# ATM90E2x-DB.net
KiCad netlist of a schematic drawn in Altium Designer
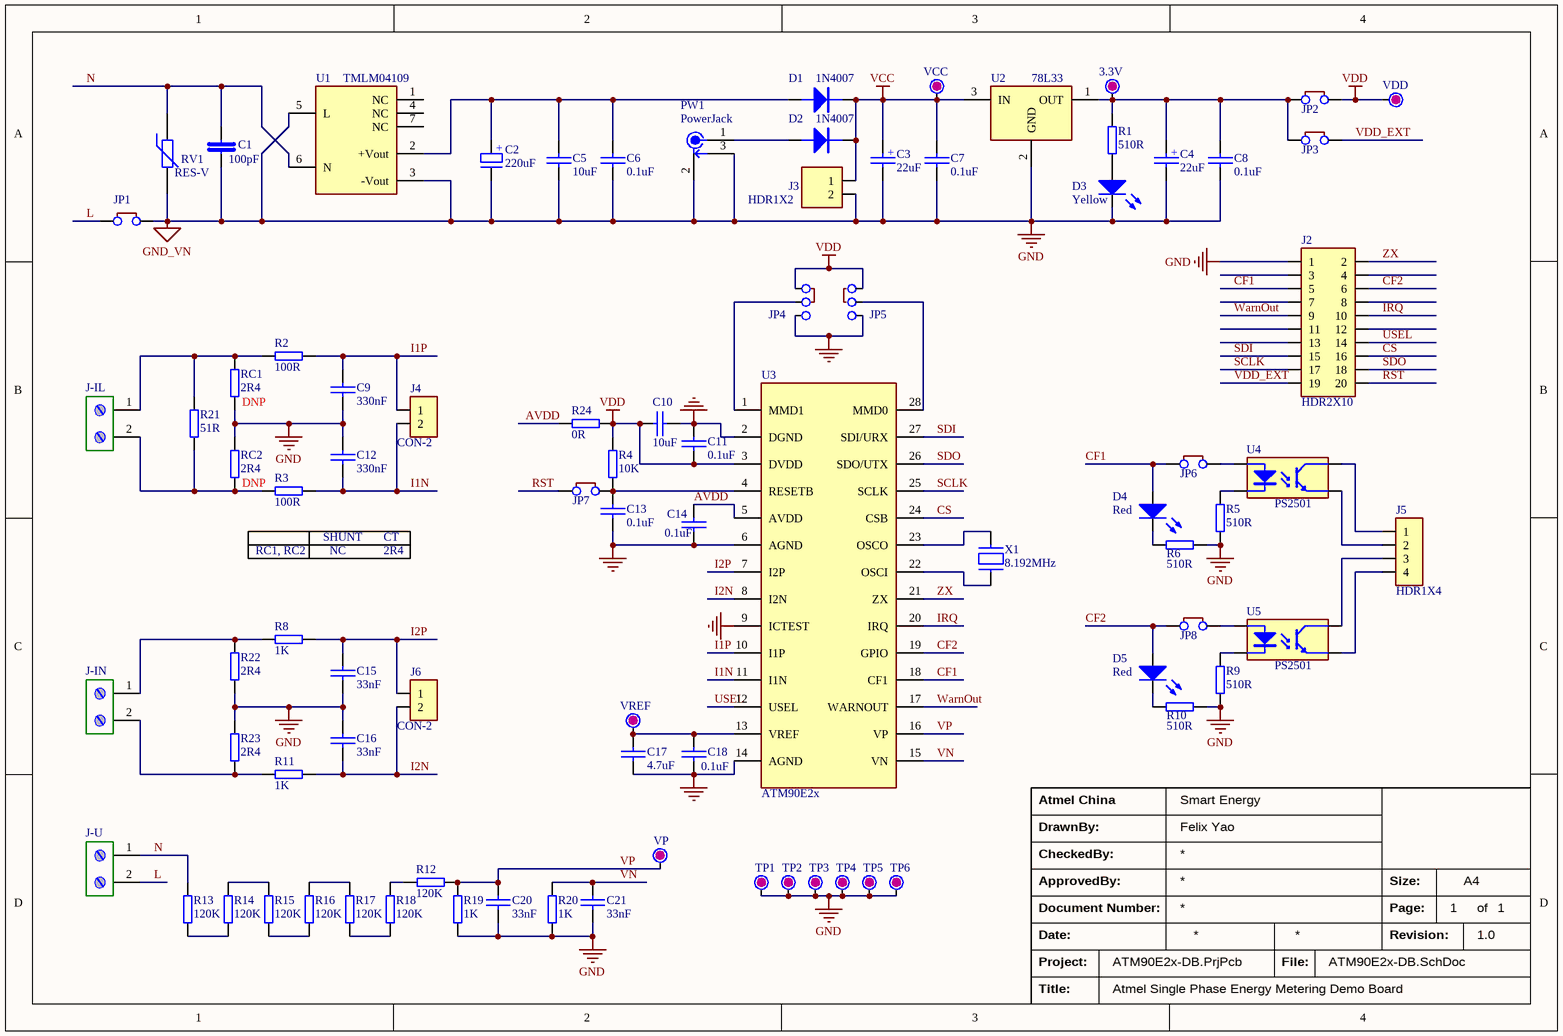
[diagram p0: ATM90E2x-DB.SchDoc]

(export (version "E")
  (design (tool "Eeschema 10.0.6"))
  (components
    (comp (ref "3.3V")
      (value "TEST-POINT")
      (footprint "TP")
      (libsource (lib "SchLib(AD10)") (part "TEST-POINT"))
    )
    (comp (ref "C1")
      (value "100pF")
      (footprint "C_FILM_600")
      (libsource (lib "SchLib(AD10)") (part "CAP-FILM"))
    )
    (comp (ref "C2")
      (value "220uF")
      (footprint "C_ALUM_MIX_10x10")
      (libsource (lib "SchLib(AD10)") (part "CAP-ALUM"))
    )
    (comp (ref "C3")
      (value "22uF")
      (footprint "C_TANT_B3528")
      (libsource (lib "SchLib(AD10)") (part "CAP-TANT"))
    )
    (comp (ref "C4")
      (value "22uF")
      (footprint "C_TANT_B3528")
      (libsource (lib "SchLib(AD10)") (part "CAP-TANT"))
    )
    (comp (ref "C5") (value "10uF") (footprint "C0805") (libsource (lib "SchLib(AD10)") (part "CAP")))
    (comp (ref "C6") (value "0.1uF") (footprint "C0805") (libsource (lib "SchLib(AD10)") (part "CAP")))
    (comp (ref "C7") (value "0.1uF") (footprint "C0805") (libsource (lib "SchLib(AD10)") (part "CAP")))
    (comp (ref "C8") (value "0.1uF") (footprint "C0805") (libsource (lib "SchLib(AD10)") (part "CAP")))
    (comp (ref "C9") (value "330nF") (footprint "C0805") (libsource (lib "SchLib(AD10)") (part "CAP")))
    (comp (ref "C10") (value "10uF") (footprint "C0805") (libsource (lib "SchLib(AD10)") (part "CAP")))
    (comp (ref "C11") (value "0.1uF") (footprint "C0603") (libsource (lib "SchLib(AD10)") (part "CAP")))
    (comp (ref "C12") (value "330nF") (footprint "C0805") (libsource (lib "SchLib(AD10)") (part "CAP")))
    (comp (ref "C13") (value "0.1uF") (footprint "C0603") (libsource (lib "SchLib(AD10)") (part "CAP")))
    (comp (ref "C14") (value "0.1uF") (footprint "C0603") (libsource (lib "SchLib(AD10)") (part "CAP")))
    (comp (ref "C15") (value "33nF") (footprint "C0805") (libsource (lib "SchLib(AD10)") (part "CAP")))
    (comp (ref "C16") (value "33nF") (footprint "C0805") (libsource (lib "SchLib(AD10)") (part "CAP")))
    (comp (ref "C17") (value "4.7uF") (footprint "C0805") (libsource (lib "SchLib(AD10)") (part "CAP")))
    (comp (ref "C18") (value "0.1uF") (footprint "C0603") (libsource (lib "SchLib(AD10)") (part "CAP")))
    (comp (ref "C20") (value "33nF") (footprint "C0805") (libsource (lib "SchLib(AD10)") (part "CAP")))
    (comp (ref "C21") (value "33nF") (footprint "C0805") (libsource (lib "SchLib(AD10)") (part "CAP")))
    (comp (ref "D1")
      (value "1N4007")
      (footprint "SMA DO-214AC")
      (libsource (lib "SchLib(AD10)") (part "DIODE"))
    )
    (comp (ref "D2")
      (value "1N4007")
      (footprint "SMA DO-214AC")
      (libsource (lib "SchLib(AD10)") (part "DIODE"))
    )
    (comp (ref "D3") (value "Yellow") (footprint "LED-0805Y") (libsource (lib "SchLib(AD10)") (part "LED")))
    (comp (ref "D4") (value "Red") (footprint "LED-0805R") (libsource (lib "SchLib(AD10)") (part "LED")))
    (comp (ref "D5") (value "Red") (footprint "LED-0805R") (libsource (lib "SchLib(AD10)") (part "LED")))
    (comp (ref "J-IL")
      (value "~")
      (footprint "TE-1776119-2")
      (libsource (lib "SchLib(AD10)") (part "Terminal-Screw-2"))
    )
    (comp (ref "J-IN")
      (value "~")
      (footprint "TE-1776119-2")
      (libsource (lib "SchLib(AD10)") (part "Terminal-Screw-2"))
    )
    (comp (ref "J-U")
      (value "~")
      (footprint "TE-282843-2")
      (libsource (lib "SchLib(AD10)") (part "Terminal-Screw-2"))
    )
    (comp (ref "J2")
      (value "HDR2X10")
      (footprint "HDR2X10")
      (libsource (lib "SchLib(AD10)") (part "HDR2X10"))
    )
    (comp (ref "J3") (value "HDR1X2") (footprint "HDR1X2") (libsource (lib "SchLib(AD10)") (part "HDR1X2")))
    (comp (ref "J4")
      (value "CON-2")
      (footprint "HDR1X2(uper)")
      (libsource (lib "SchLib(AD10)") (part "CON-2"))
    )
    (comp (ref "J5") (value "HDR1X4") (footprint "HDR1X4") (libsource (lib "SchLib(AD10)") (part "HDR1X4")))
    (comp (ref "J6")
      (value "CON-2")
      (footprint "HDR1X2(uper)")
      (libsource (lib "SchLib(AD10)") (part "CON-2"))
    )
    (comp (ref "JP1") (value "JMP") (footprint "JMP-SMD") (libsource (lib "SchLib(AD10)") (part "JMP")))
    (comp (ref "JP2") (value "JMP") (footprint "JMP") (libsource (lib "SchLib(AD10)") (part "JMP")))
    (comp (ref "JP3") (value "JMP") (footprint "JMP") (libsource (lib "SchLib(AD10)") (part "JMP")))
    (comp (ref "JP4") (value "JMP3") (footprint "JMP3") (libsource (lib "SchLib(AD10)") (part "JMP3")))
    (comp (ref "JP5") (value "JMP3") (footprint "JMP3") (libsource (lib "SchLib(AD10)") (part "JMP3")))
    (comp (ref "JP6") (value "JMP") (footprint "JMP") (libsource (lib "SchLib(AD10)") (part "JMP")))
    (comp (ref "JP7") (value "JMP") (footprint "JMP") (libsource (lib "SchLib(AD10)") (part "JMP")))
    (comp (ref "JP8") (value "JMP") (footprint "JMP") (libsource (lib "SchLib(AD10)") (part "JMP")))
    (comp (ref "PW1")
      (value "PowerJack")
      (footprint "PowerJacket2.5")
      (libsource (lib "SchLib(AD10)") (part "PowerJack"))
    )
    (comp (ref "R1") (value "510R") (footprint "R0805") (libsource (lib "SchLib(AD10)") (part "RES")))
    (comp (ref "R2") (value "100R") (footprint "R0805") (libsource (lib "SchLib(AD10)") (part "RES")))
    (comp (ref "R3") (value "100R") (footprint "R0805") (libsource (lib "SchLib(AD10)") (part "RES")))
    (comp (ref "R4") (value "10K") (footprint "R0603") (libsource (lib "SchLib(AD10)") (part "RES")))
    (comp (ref "R5") (value "510R") (footprint "R0805") (libsource (lib "SchLib(AD10)") (part "RES")))
    (comp (ref "R6") (value "510R") (footprint "R0805") (libsource (lib "SchLib(AD10)") (part "RES")))
    (comp (ref "R8") (value "1K") (footprint "R0805") (libsource (lib "SchLib(AD10)") (part "RES")))
    (comp (ref "R9") (value "510R") (footprint "R0805") (libsource (lib "SchLib(AD10)") (part "RES")))
    (comp (ref "R10") (value "510R") (footprint "R0805") (libsource (lib "SchLib(AD10)") (part "RES")))
    (comp (ref "R11") (value "1K") (footprint "R0805") (libsource (lib "SchLib(AD10)") (part "RES")))
    (comp (ref "R12") (value "120K") (footprint "R1206") (libsource (lib "SchLib(AD10)") (part "RES")))
    (comp (ref "R13") (value "120K") (footprint "R1206") (libsource (lib "SchLib(AD10)") (part "RES")))
    (comp (ref "R14") (value "120K") (footprint "R1206") (libsource (lib "SchLib(AD10)") (part "RES")))
    (comp (ref "R15") (value "120K") (footprint "R1206") (libsource (lib "SchLib(AD10)") (part "RES")))
    (comp (ref "R16") (value "120K") (footprint "R1206") (libsource (lib "SchLib(AD10)") (part "RES")))
    (comp (ref "R17") (value "120K") (footprint "R1206") (libsource (lib "SchLib(AD10)") (part "RES")))
    (comp (ref "R18") (value "120K") (footprint "R1206") (libsource (lib "SchLib(AD10)") (part "RES")))
    (comp (ref "R19") (value "1K") (footprint "R0805") (libsource (lib "SchLib(AD10)") (part "RES")))
    (comp (ref "R20") (value "1K") (footprint "R0805") (libsource (lib "SchLib(AD10)") (part "RES")))
    (comp (ref "R21") (value "51R") (footprint "R0805") (libsource (lib "SchLib(AD10)") (part "RES")))
    (comp (ref "R22") (value "2R4") (footprint "R0805") (libsource (lib "SchLib(AD10)") (part "RES")))
    (comp (ref "R23") (value "2R4") (footprint "R0805") (libsource (lib "SchLib(AD10)") (part "RES")))
    (comp (ref "R24") (value "0R") (footprint "R0603") (libsource (lib "SchLib(AD10)") (part "RES")))
    (comp (ref "RC1") (value "2R4") (footprint "R0805") (libsource (lib "SchLib(AD10)") (part "RES")))
    (comp (ref "RC2") (value "2R4") (footprint "R0805") (libsource (lib "SchLib(AD10)") (part "RES")))
    (comp (ref "RV1")
      (value "RES-V")
      (footprint "VDRS10P510BSE")
      (libsource (lib "SchLib(AD10)") (part "RES-V"))
    )
    (comp (ref "TP1") (value "GND") (footprint "TP") (libsource (lib "SchLib(AD10)") (part "TEST-POINT")))
    (comp (ref "TP2") (value "GND") (footprint "TP") (libsource (lib "SchLib(AD10)") (part "TEST-POINT")))
    (comp (ref "TP3") (value "GND") (footprint "TP") (libsource (lib "SchLib(AD10)") (part "TEST-POINT")))
    (comp (ref "TP4") (value "GND") (footprint "TP") (libsource (lib "SchLib(AD10)") (part "TEST-POINT")))
    (comp (ref "TP5") (value "GND") (footprint "TP-SMD") (libsource (lib "SchLib(AD10)") (part "TEST-POINT")))
    (comp (ref "TP6") (value "GND") (footprint "TP-SMD") (libsource (lib "SchLib(AD10)") (part "TEST-POINT")))
    (comp (ref "U1")
      (value "TMLM04109")
      (footprint "TMLM04112")
      (libsource (lib "SchLib(AD10)") (part "TMLM04112"))
    )
    (comp (ref "U2") (value "78L33") (footprint "SOT-89") (libsource (lib "SchLib(AD10)") (part "78LXX")))
    (comp (ref "U3")
      (value "ATM90E2x")
      (footprint "SSOP-28")
      (description "ATM90E25")
      (libsource (lib "SchLib(AD10)") (part "ATM90E25"))
    )
    (comp (ref "U4")
      (value "PS2501")
      (footprint "PS2501L-1")
      (description "NEC2501")
      (libsource (lib "SchLib(AD10)") (part "NEC2501"))
    )
    (comp (ref "U5")
      (value "PS2501")
      (footprint "PS2501L-1")
      (description "NEC2501")
      (libsource (lib "SchLib(AD10)") (part "NEC2501"))
    )
    (comp (ref "VCC")
      (value "TEST-POINT")
      (footprint "TP")
      (libsource (lib "SchLib(AD10)") (part "TEST-POINT"))
    )
    (comp (ref "VDD")
      (value "TEST-POINT")
      (footprint "TP")
      (libsource (lib "SchLib(AD10)") (part "TEST-POINT"))
    )
    (comp (ref "VP")
      (value "TEST-POINT")
      (footprint "TP")
      (libsource (lib "SchLib(AD10)") (part "TEST-POINT"))
    )
    (comp (ref "VREF")
      (value "TEST-POINT")
      (footprint "TP")
      (libsource (lib "SchLib(AD10)") (part "TEST-POINT"))
    )
    (comp (ref "X1")
      (value "8.192MHz")
      (footprint "XTAL-MIX-49")
      (libsource (lib "SchLib(AD10)") (part "XTAL-T"))
    )
  )
  (nets
    (net (code "1") (name "/AVDD") (class "Default")
      (node (ref "C14") (pin "2") (pintype "passive"))
      (node (ref "R24") (pin "1") (pinfunction "1_1") (pintype "passive"))
      (node (ref "U3") (pin "5") (pinfunction "AVDD_5") (pintype "passive"))
    )
    (net (code "2") (name "/CF1") (class "Default")
      (node (ref "D4") (pin "A") (pinfunction "A_A") (pintype "passive"))
      (node (ref "J2") (pin "5") (pinfunction "5_5") (pintype "passive"))
      (node (ref "JP6") (pin "1") (pinfunction "1_1") (pintype "passive"))
      (node (ref "U3") (pin "18") (pinfunction "CF1_18") (pintype "passive"))
    )
    (net (code "3") (name "/CF2") (class "Default")
      (node (ref "D5") (pin "A") (pinfunction "A_A") (pintype "passive"))
      (node (ref "J2") (pin "6") (pinfunction "6_6") (pintype "passive"))
      (node (ref "JP8") (pin "1") (pinfunction "1_1") (pintype "passive"))
      (node (ref "U3") (pin "19") (pinfunction "GPIO_19") (pintype "passive"))
    )
    (net (code "4") (name "/CS") (class "Default")
      (node (ref "J2") (pin "16") (pinfunction "16_16") (pintype "passive"))
      (node (ref "U3") (pin "24") (pinfunction "CSB_24") (pintype "passive"))
    )
    (net (code "5") (name "/I1N") (class "Default")
      (node (ref "C12") (pin "1") (pintype "passive"))
      (node (ref "J4") (pin "2") (pinfunction "2_2") (pintype "passive"))
      (node (ref "R3") (pin "1") (pinfunction "1_1") (pintype "passive"))
      (node (ref "U3") (pin "11") (pinfunction "I1N_11") (pintype "passive"))
    )
    (net (code "6") (name "/I1P") (class "Default")
      (node (ref "C9") (pin "2") (pintype "passive"))
      (node (ref "J4") (pin "1") (pinfunction "1_1") (pintype "passive"))
      (node (ref "R2") (pin "1") (pinfunction "1_1") (pintype "passive"))
      (node (ref "U3") (pin "10") (pinfunction "I1P_10") (pintype "passive"))
    )
    (net (code "7") (name "/I2N") (class "Default")
      (node (ref "C16") (pin "1") (pintype "passive"))
      (node (ref "J6") (pin "2") (pinfunction "2_2") (pintype "passive"))
      (node (ref "R11") (pin "1") (pinfunction "1_1") (pintype "passive"))
      (node (ref "U3") (pin "8") (pinfunction "I2N_8") (pintype "passive"))
    )
    (net (code "8") (name "/I2P") (class "Default")
      (node (ref "C15") (pin "2") (pintype "passive"))
      (node (ref "J6") (pin "1") (pinfunction "1_1") (pintype "passive"))
      (node (ref "R8") (pin "1") (pinfunction "1_1") (pintype "passive"))
      (node (ref "U3") (pin "7") (pinfunction "I2P_7") (pintype "passive"))
    )
    (net (code "9") (name "/IRQ") (class "Default")
      (node (ref "J2") (pin "10") (pinfunction "10_10") (pintype "passive"))
      (node (ref "U3") (pin "20") (pinfunction "IRQ_20") (pintype "passive"))
    )
    (net (code "10") (name "/L") (class "Default")
      (node (ref "J-U") (pin "2") (pinfunction "2_2") (pintype "passive"))
      (node (ref "JP1") (pin "1") (pinfunction "1_1") (pintype "passive"))
    )
    (net (code "11") (name "/N") (class "Default")
      (node (ref "C1") (pin "1") (pintype "passive"))
      (node (ref "J-U") (pin "1") (pinfunction "1_1") (pintype "passive"))
      (node (ref "R13") (pin "1") (pinfunction "1_1") (pintype "passive"))
      (node (ref "RV1") (pin "1") (pinfunction "1_1") (pintype "passive"))
      (node (ref "U1") (pin "6") (pinfunction "N_6") (pintype "passive"))
    )
    (net (code "12") (name "/RST") (class "Default")
      (node (ref "J2") (pin "20") (pinfunction "20_20") (pintype "passive"))
      (node (ref "JP7") (pin "1") (pinfunction "1_1") (pintype "passive"))
    )
    (net (code "13") (name "/SCLK") (class "Default")
      (node (ref "J2") (pin "17") (pinfunction "17_17") (pintype "passive"))
      (node (ref "U3") (pin "25") (pinfunction "SCLK_25") (pintype "passive"))
    )
    (net (code "14") (name "/SDI") (class "Default")
      (node (ref "J2") (pin "15") (pinfunction "15_15") (pintype "passive"))
      (node (ref "U3") (pin "27") (pinfunction "SDI/URX_27") (pintype "passive"))
    )
    (net (code "15") (name "/SDO") (class "Default")
      (node (ref "J2") (pin "18") (pinfunction "18_18") (pintype "passive"))
      (node (ref "U3") (pin "26") (pinfunction "SDO/UTX_26") (pintype "passive"))
    )
    (net (code "16") (name "/USEL") (class "Default")
      (node (ref "J2") (pin "14") (pinfunction "14_14") (pintype "passive"))
      (node (ref "U3") (pin "12") (pinfunction "USEL_12") (pintype "passive"))
    )
    (net (code "17") (name "/VDD_EXT") (class "Default")
      (node (ref "J2") (pin "19") (pinfunction "19_19") (pintype "passive"))
      (node (ref "JP3") (pin "2") (pinfunction "2_2") (pintype "passive"))
    )
    (net (code "18") (name "/VN") (class "Default")
      (node (ref "C21") (pin "2") (pintype "passive"))
      (node (ref "R20") (pin "2") (pinfunction "2_2") (pintype "passive"))
      (node (ref "U3") (pin "15") (pinfunction "VN_15") (pintype "passive"))
    )
    (net (code "19") (name "/VP") (class "Default")
      (node (ref "C20") (pin "2") (pintype "passive"))
      (node (ref "R12") (pin "2") (pinfunction "2_2") (pintype "passive"))
      (node (ref "R19") (pin "2") (pinfunction "2_2") (pintype "passive"))
      (node (ref "U3") (pin "16") (pinfunction "VP_16") (pintype "passive"))
      (node (ref "VP") (pin "1") (pinfunction "1_1") (pintype "passive"))
    )
    (net (code "20") (name "/WarnOut") (class "Default")
      (node (ref "J2") (pin "9") (pinfunction "9_9") (pintype "passive"))
      (node (ref "U3") (pin "17") (pinfunction "WARNOUT_17") (pintype "passive"))
    )
    (net (code "21") (name "/ZX") (class "Default")
      (node (ref "J2") (pin "2") (pinfunction "2_2") (pintype "passive"))
      (node (ref "U3") (pin "21") (pinfunction "ZX_21") (pintype "passive"))
    )
    (net (code "22") (name "GND") (class "Default")
      (node (ref "C1") (pin "2") (pintype "passive"))
      (node (ref "C10") (pin "2") (pintype "passive"))
      (node (ref "C11") (pin "2") (pintype "passive"))
      (node (ref "C12") (pin "2") (pintype "passive"))
      (node (ref "C13") (pin "1") (pintype "passive"))
      (node (ref "C14") (pin "1") (pintype "passive"))
      (node (ref "C15") (pin "1") (pintype "passive"))
      (node (ref "C16") (pin "2") (pintype "passive"))
      (node (ref "C17") (pin "1") (pintype "passive"))
      (node (ref "C18") (pin "1") (pintype "passive"))
      (node (ref "C2") (pin "2") (pinfunction "2_2") (pintype "passive"))
      (node (ref "C20") (pin "1") (pintype "passive"))
      (node (ref "C21") (pin "1") (pintype "passive"))
      (node (ref "C3") (pin "2") (pintype "passive"))
      (node (ref "C4") (pin "2") (pintype "passive"))
      (node (ref "C5") (pin "1") (pintype "passive"))
      (node (ref "C6") (pin "1") (pintype "passive"))
      (node (ref "C7") (pin "1") (pintype "passive"))
      (node (ref "C8") (pin "1") (pintype "passive"))
      (node (ref "C9") (pin "1") (pintype "passive"))
      (node (ref "D3") (pin "K") (pinfunction "K_K") (pintype "passive"))
      (node (ref "J2") (pin "1") (pinfunction "1_1") (pintype "passive"))
      (node (ref "J3") (pin "2") (pinfunction "2_2") (pintype "passive"))
      (node (ref "JP1") (pin "2") (pinfunction "2_2") (pintype "passive"))
      (node (ref "JP4") (pin "3") (pinfunction "3_3") (pintype "passive"))
      (node (ref "JP5") (pin "3") (pinfunction "3_3") (pintype "passive"))
      (node (ref "PW1") (pin "2") (pinfunction "2_2") (pintype "passive"))
      (node (ref "PW1") (pin "3") (pinfunction "3_3") (pintype "passive"))
      (node (ref "R10") (pin "1") (pinfunction "1_1") (pintype "passive"))
      (node (ref "R19") (pin "1") (pinfunction "1_1") (pintype "passive"))
      (node (ref "R20") (pin "1") (pinfunction "1_1") (pintype "passive"))
      (node (ref "R22") (pin "1") (pinfunction "1_1") (pintype "passive"))
      (node (ref "R23") (pin "2") (pinfunction "2_2") (pintype "passive"))
      (node (ref "R5") (pin "1") (pinfunction "1_1") (pintype "passive"))
      (node (ref "R6") (pin "1") (pinfunction "1_1") (pintype "passive"))
      (node (ref "R9") (pin "1") (pinfunction "1_1") (pintype "passive"))
      (node (ref "RC1") (pin "1") (pinfunction "1_1") (pintype "passive"))
      (node (ref "RC2") (pin "2") (pinfunction "2_2") (pintype "passive"))
      (node (ref "RV1") (pin "2") (pinfunction "2_2") (pintype "passive"))
      (node (ref "TP1") (pin "1") (pinfunction "1_1") (pintype "passive"))
      (node (ref "TP2") (pin "1") (pinfunction "1_1") (pintype "passive"))
      (node (ref "TP3") (pin "1") (pinfunction "1_1") (pintype "passive"))
      (node (ref "TP4") (pin "1") (pinfunction "1_1") (pintype "passive"))
      (node (ref "TP5") (pin "1") (pinfunction "1_1") (pintype "passive"))
      (node (ref "TP6") (pin "1") (pinfunction "1_1") (pintype "passive"))
      (node (ref "U1") (pin "3") (pinfunction "-Vout_3") (pintype "passive"))
      (node (ref "U1") (pin "5") (pinfunction "L_5") (pintype "passive"))
      (node (ref "U2") (pin "2") (pinfunction "GND_2") (pintype "passive"))
      (node (ref "U3") (pin "14") (pinfunction "AGND_14") (pintype "passive"))
      (node (ref "U3") (pin "2") (pinfunction "DGND_2") (pintype "passive"))
      (node (ref "U3") (pin "6") (pinfunction "AGND_6") (pintype "passive"))
      (node (ref "U3") (pin "9") (pinfunction "ICTEST_9") (pintype "passive"))
    )
    (net (code "23") (name "Net-(D2-PadA)") (class "Default")
      (node (ref "D2") (pin "A") (pintype "passive"))
      (node (ref "PW1") (pin "1") (pinfunction "1_1") (pintype "passive"))
    )
    (net (code "24") (name "Net-(D3-PadA)") (class "Default")
      (node (ref "D3") (pin "A") (pinfunction "A_A") (pintype "passive"))
      (node (ref "R1") (pin "1") (pinfunction "1_1") (pintype "passive"))
    )
    (net (code "25") (name "Net-(D4-PadK)") (class "Default")
      (node (ref "D4") (pin "K") (pinfunction "K_K") (pintype "passive"))
      (node (ref "R6") (pin "2") (pinfunction "2_2") (pintype "passive"))
    )
    (net (code "26") (name "Net-(D5-PadK)") (class "Default")
      (node (ref "D5") (pin "K") (pinfunction "K_K") (pintype "passive"))
      (node (ref "R10") (pin "2") (pinfunction "2_2") (pintype "passive"))
    )
    (net (code "27") (name "Net-(J-IL-Pad1)") (class "Default")
      (node (ref "J-IL") (pin "1") (pinfunction "1_1") (pintype "passive"))
      (node (ref "R2") (pin "2") (pinfunction "2_2") (pintype "passive"))
      (node (ref "R21") (pin "2") (pinfunction "2_2") (pintype "passive"))
      (node (ref "RC1") (pin "2") (pinfunction "2_2") (pintype "passive"))
    )
    (net (code "28") (name "Net-(J-IL-Pad2)") (class "Default")
      (node (ref "J-IL") (pin "2") (pinfunction "2_2") (pintype "passive"))
      (node (ref "R21") (pin "1") (pinfunction "1_1") (pintype "passive"))
      (node (ref "R3") (pin "2") (pinfunction "2_2") (pintype "passive"))
      (node (ref "RC2") (pin "1") (pinfunction "1_1") (pintype "passive"))
    )
    (net (code "29") (name "Net-(J-IN-Pad1)") (class "Default")
      (node (ref "J-IN") (pin "1") (pinfunction "1_1") (pintype "passive"))
      (node (ref "R22") (pin "2") (pinfunction "2_2") (pintype "passive"))
      (node (ref "R8") (pin "2") (pinfunction "2_2") (pintype "passive"))
    )
    (net (code "30") (name "Net-(J-IN-Pad2)") (class "Default")
      (node (ref "J-IN") (pin "2") (pinfunction "2_2") (pintype "passive"))
      (node (ref "R11") (pin "2") (pinfunction "2_2") (pintype "passive"))
      (node (ref "R23") (pin "1") (pinfunction "1_1") (pintype "passive"))
    )
    (net (code "31") (name "Net-(R12-Pad1)") (class "Default")
      (node (ref "R12") (pin "1") (pinfunction "1_1") (pintype "passive"))
      (node (ref "R18") (pin "1") (pinfunction "1_1") (pintype "passive"))
    )
    (net (code "32") (name "Net-(R13-Pad2)") (class "Default")
      (node (ref "R13") (pin "2") (pinfunction "2_2") (pintype "passive"))
      (node (ref "R14") (pin "2") (pinfunction "2_2") (pintype "passive"))
    )
    (net (code "33") (name "Net-(R14-Pad1)") (class "Default")
      (node (ref "R14") (pin "1") (pinfunction "1_1") (pintype "passive"))
      (node (ref "R15") (pin "1") (pinfunction "1_1") (pintype "passive"))
    )
    (net (code "34") (name "Net-(R15-Pad2)") (class "Default")
      (node (ref "R15") (pin "2") (pinfunction "2_2") (pintype "passive"))
      (node (ref "R16") (pin "2") (pinfunction "2_2") (pintype "passive"))
    )
    (net (code "35") (name "Net-(R16-Pad1)") (class "Default")
      (node (ref "R16") (pin "1") (pinfunction "1_1") (pintype "passive"))
      (node (ref "R17") (pin "1") (pinfunction "1_1") (pintype "passive"))
    )
    (net (code "36") (name "Net-(R17-Pad2)") (class "Default")
      (node (ref "R17") (pin "2") (pinfunction "2_2") (pintype "passive"))
      (node (ref "R18") (pin "2") (pinfunction "2_2") (pintype "passive"))
    )
    (net (code "37") (name "Net-(U1-+Vout)") (class "Default")
      (node (ref "C2") (pin "1") (pinfunction "1_1") (pintype "passive"))
      (node (ref "C5") (pin "2") (pintype "passive"))
      (node (ref "C6") (pin "2") (pintype "passive"))
      (node (ref "D1") (pin "A") (pintype "passive"))
      (node (ref "U1") (pin "2") (pinfunction "+Vout_2") (pintype "passive"))
    )
    (net (code "38") (name "Net-(U2-OUT)") (class "Default")
      (node (ref "3.3V") (pin "1") (pinfunction "1_1") (pintype "passive"))
      (node (ref "C4") (pin "1") (pintype "passive"))
      (node (ref "C8") (pin "2") (pintype "passive"))
      (node (ref "JP2") (pin "1") (pinfunction "1_1") (pintype "passive"))
      (node (ref "JP3") (pin "1") (pinfunction "1_1") (pintype "passive"))
      (node (ref "R1") (pin "2") (pinfunction "2_2") (pintype "passive"))
      (node (ref "U2") (pin "1") (pinfunction "OUT_1") (pintype "passive"))
    )
    (net (code "39") (name "Net-(U3-MMD0)") (class "Default")
      (node (ref "JP5") (pin "2") (pinfunction "2_2") (pintype "passive"))
      (node (ref "U3") (pin "28") (pinfunction "MMD0_28") (pintype "passive"))
    )
    (net (code "40") (name "Net-(U3-MMD1)") (class "Default")
      (node (ref "JP4") (pin "2") (pinfunction "2_2") (pintype "passive"))
      (node (ref "U3") (pin "1") (pinfunction "MMD1_1") (pintype "passive"))
    )
    (net (code "41") (name "Net-(U3-OSCI)") (class "Default")
      (node (ref "U3") (pin "22") (pinfunction "OSCI_22") (pintype "passive"))
      (node (ref "X1") (pin "2") (pintype "passive"))
    )
    (net (code "42") (name "Net-(U3-OSCO)") (class "Default")
      (node (ref "U3") (pin "23") (pinfunction "OSCO_23") (pintype "passive"))
      (node (ref "X1") (pin "1") (pintype "passive"))
    )
    (net (code "43") (name "Net-(U3-RESETB)") (class "Default")
      (node (ref "C13") (pin "2") (pintype "passive"))
      (node (ref "JP7") (pin "2") (pinfunction "2_2") (pintype "passive"))
      (node (ref "R4") (pin "1") (pinfunction "1_1") (pintype "passive"))
      (node (ref "U3") (pin "4") (pinfunction "RESETB_4") (pintype "passive"))
    )
    (net (code "44") (name "Net-(U3-VREF)") (class "Default")
      (node (ref "C17") (pin "2") (pintype "passive"))
      (node (ref "C18") (pin "2") (pintype "passive"))
      (node (ref "U3") (pin "13") (pinfunction "VREF_13") (pintype "passive"))
      (node (ref "VREF") (pin "1") (pinfunction "1_1") (pintype "passive"))
    )
    (net (code "45") (name "Net-(U4-A)") (class "Default")
      (node (ref "JP6") (pin "2") (pinfunction "2_2") (pintype "passive"))
      (node (ref "U4") (pin "1") (pinfunction "A_1") (pintype "passive"))
    )
    (net (code "46") (name "Net-(U4-C)") (class "Default")
      (node (ref "J5") (pin "1") (pinfunction "1_1") (pintype "passive"))
      (node (ref "U4") (pin "4") (pinfunction "C_4") (pintype "passive"))
    )
    (net (code "47") (name "Net-(U4-E)") (class "Default")
      (node (ref "J5") (pin "2") (pinfunction "2_2") (pintype "passive"))
      (node (ref "U4") (pin "3") (pinfunction "E_3") (pintype "passive"))
    )
    (net (code "48") (name "Net-(U4-K)") (class "Default")
      (node (ref "R5") (pin "2") (pinfunction "2_2") (pintype "passive"))
      (node (ref "U4") (pin "2") (pinfunction "K_2") (pintype "passive"))
    )
    (net (code "49") (name "Net-(U5-A)") (class "Default")
      (node (ref "JP8") (pin "2") (pinfunction "2_2") (pintype "passive"))
      (node (ref "U5") (pin "1") (pinfunction "A_1") (pintype "passive"))
    )
    (net (code "50") (name "Net-(U5-C)") (class "Default")
      (node (ref "J5") (pin "3") (pinfunction "3_3") (pintype "passive"))
      (node (ref "U5") (pin "4") (pinfunction "C_4") (pintype "passive"))
    )
    (net (code "51") (name "Net-(U5-E)") (class "Default")
      (node (ref "J5") (pin "4") (pinfunction "4_4") (pintype "passive"))
      (node (ref "U5") (pin "3") (pinfunction "E_3") (pintype "passive"))
    )
    (net (code "52") (name "Net-(U5-K)") (class "Default")
      (node (ref "R9") (pin "2") (pinfunction "2_2") (pintype "passive"))
      (node (ref "U5") (pin "2") (pinfunction "K_2") (pintype "passive"))
    )
    (net (code "53") (name "VCC") (class "Default")
      (node (ref "C3") (pin "1") (pintype "passive"))
      (node (ref "C7") (pin "2") (pintype "passive"))
      (node (ref "D1") (pin "K") (pintype "passive"))
      (node (ref "D2") (pin "K") (pintype "passive"))
      (node (ref "J3") (pin "1") (pinfunction "1_1") (pintype "passive"))
      (node (ref "U2") (pin "3") (pinfunction "IN_3") (pintype "passive"))
      (node (ref "VCC") (pin "1") (pinfunction "1_1") (pintype "passive"))
    )
    (net (code "54") (name "VDD") (class "Default")
      (node (ref "C10") (pin "1") (pintype "passive"))
      (node (ref "C11") (pin "1") (pintype "passive"))
      (node (ref "JP2") (pin "2") (pinfunction "2_2") (pintype "passive"))
      (node (ref "JP4") (pin "1") (pinfunction "1_1") (pintype "passive"))
      (node (ref "JP5") (pin "1") (pinfunction "1_1") (pintype "passive"))
      (node (ref "R24") (pin "2") (pinfunction "2_2") (pintype "passive"))
      (node (ref "R4") (pin "2") (pinfunction "2_2") (pintype "passive"))
      (node (ref "U3") (pin "3") (pinfunction "DVDD_3") (pintype "passive"))
      (node (ref "VDD") (pin "1") (pinfunction "1_1") (pintype "passive"))
    )
    (net (code "55") (name "unconnected-(J2-Pad3)") (class "Default")
      (node (ref "J2") (pin "3") (pinfunction "3_3") (pintype "passive"))
    )
    (net (code "56") (name "unconnected-(J2-Pad4)") (class "Default")
      (node (ref "J2") (pin "4") (pinfunction "4_4") (pintype "passive"))
    )
    (net (code "57") (name "unconnected-(J2-Pad7)") (class "Default")
      (node (ref "J2") (pin "7") (pinfunction "7_7") (pintype "passive"))
    )
    (net (code "58") (name "unconnected-(J2-Pad8)") (class "Default")
      (node (ref "J2") (pin "8") (pinfunction "8_8") (pintype "passive"))
    )
    (net (code "59") (name "unconnected-(J2-Pad11)") (class "Default")
      (node (ref "J2") (pin "11") (pinfunction "11_11") (pintype "passive"))
    )
    (net (code "60") (name "unconnected-(J2-Pad12)") (class "Default")
      (node (ref "J2") (pin "12") (pinfunction "12_12") (pintype "passive"))
    )
    (net (code "61") (name "unconnected-(J2-Pad13)") (class "Default")
      (node (ref "J2") (pin "13") (pinfunction "13_13") (pintype "passive"))
    )
    (net (code "62") (name "unconnected-(U1-NC-Pad1)") (class "Default")
      (node (ref "U1") (pin "1") (pinfunction "NC_1") (pintype "passive"))
    )
    (net (code "63") (name "unconnected-(U1-NC-Pad4)") (class "Default")
      (node (ref "U1") (pin "4") (pinfunction "NC_4") (pintype "passive"))
    )
    (net (code "64") (name "unconnected-(U1-NC-Pad7)") (class "Default")
      (node (ref "U1") (pin "7") (pinfunction "NC_7") (pintype "passive"))
    )
  )
)
